# MotherBoard_PowerSupply.net
KiCad netlist of a schematic drawn in Altium Designer
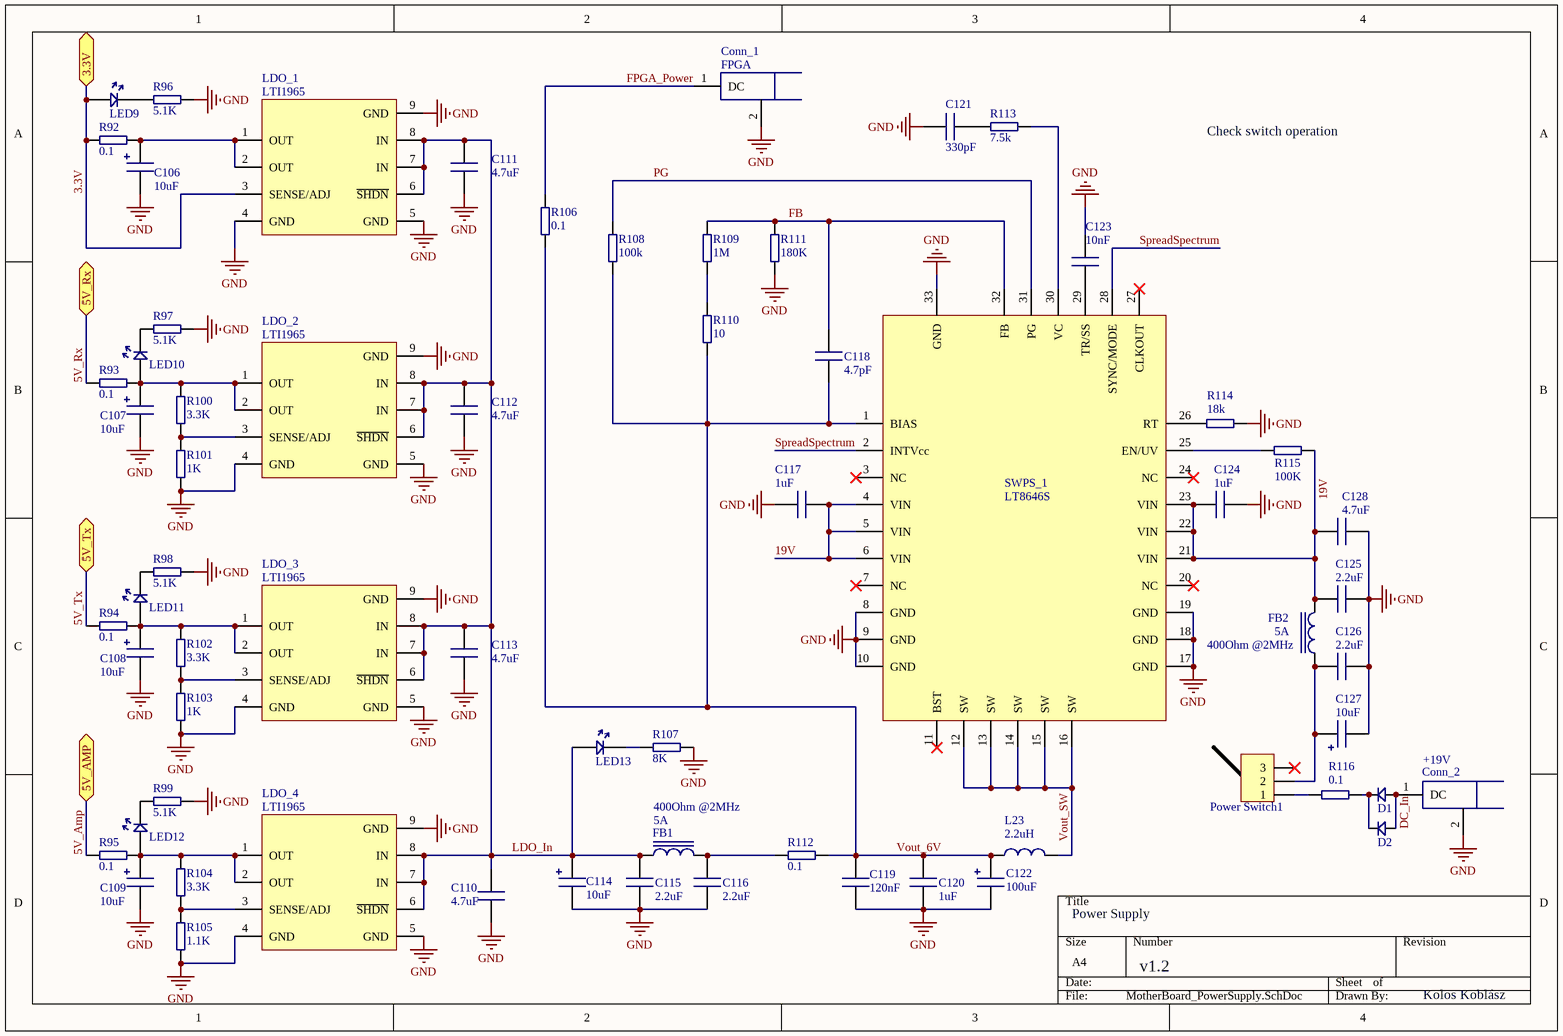
[diagram p0: MotherBoard_PowerSupply.SchDoc]

(export (version "E")
  (design (tool "Eeschema 10.0.6"))
  (components
    (comp (ref "C106")
      (value "10uF")
      (footprint "ELKO_CAP")
      (description "SMD Polarized Capacitor")
      (fields (field (name "Comment") "Cap2"))
      (libsource (lib "RadioProjectSchLib") (part "Cap2"))
    )
    (comp (ref "C107")
      (value "10uF")
      (footprint "ELKO_CAP")
      (description "SMD Polarized Capacitor")
      (fields (field (name "Comment") "Cap2"))
      (libsource (lib "RadioProjectSchLib") (part "Cap2"))
    )
    (comp (ref "C108")
      (value "10uF")
      (footprint "ELKO_CAP")
      (description "SMD Polarized Capacitor")
      (fields (field (name "Comment") "Cap2"))
      (libsource (lib "RadioProjectSchLib") (part "Cap2"))
    )
    (comp (ref "C109")
      (value "10uF")
      (footprint "ELKO_CAP")
      (description "SMD Polarized Capacitor")
      (fields (field (name "Comment") "Cap2"))
      (libsource (lib "RadioProjectSchLib") (part "Cap2"))
    )
    (comp (ref "C110")
      (value "4.7uF")
      (footprint "0805 SMD Passive")
      (description "SMD Capacitor")
      (fields (field (name "Comment") "Cap1"))
      (libsource (lib "RadioProjectSchLib") (part "Cap1"))
    )
    (comp (ref "C111")
      (value "4.7uF")
      (footprint "0805 SMD Passive")
      (description "SMD Capacitor")
      (fields (field (name "Comment") "Cap1"))
      (libsource (lib "RadioProjectSchLib") (part "Cap1"))
    )
    (comp (ref "C112")
      (value "4.7uF")
      (footprint "0805 SMD Passive")
      (description "SMD Capacitor")
      (fields (field (name "Comment") "Cap1"))
      (libsource (lib "RadioProjectSchLib") (part "Cap1"))
    )
    (comp (ref "C113")
      (value "4.7uF")
      (footprint "0805 SMD Passive")
      (description "SMD Capacitor")
      (fields (field (name "Comment") "Cap1"))
      (libsource (lib "RadioProjectSchLib") (part "Cap1"))
    )
    (comp (ref "C114")
      (value "10uF")
      (footprint "ELKO_CAP")
      (description "SMD Polarized Capacitor")
      (fields (field (name "Comment") "Cap2"))
      (libsource (lib "RadioProjectSchLib") (part "Cap2"))
    )
    (comp (ref "C115")
      (value "2.2uF")
      (footprint "0805 SMD Passive")
      (description "SMD Capacitor")
      (fields (field (name "Comment") "Cap1"))
      (libsource (lib "RadioProjectSchLib") (part "Cap1"))
    )
    (comp (ref "C116")
      (value "2.2uF")
      (footprint "0805 SMD Passive")
      (description "SMD Capacitor")
      (fields (field (name "Comment") "Cap1"))
      (libsource (lib "RadioProjectSchLib") (part "Cap1"))
    )
    (comp (ref "C117")
      (value "1uF")
      (footprint "0805 SMD Passive")
      (description "SMD Capacitor")
      (fields (field (name "Comment") "Cap1"))
      (libsource (lib "RadioProjectSchLib") (part "Cap1"))
    )
    (comp (ref "C118")
      (value "4.7pF")
      (footprint "0805 SMD Passive")
      (description "SMD Capacitor")
      (fields (field (name "Comment") "Cap1"))
      (libsource (lib "RadioProjectSchLib") (part "Cap1"))
    )
    (comp (ref "C119")
      (value "120nF")
      (footprint "0805 SMD Passive")
      (description "SMD Capacitor")
      (fields (field (name "Comment") "Cap1"))
      (libsource (lib "RadioProjectSchLib") (part "Cap1"))
    )
    (comp (ref "C120")
      (value "1uF")
      (footprint "0805 SMD Passive")
      (description "SMD Capacitor")
      (fields (field (name "Comment") "Cap1"))
      (libsource (lib "RadioProjectSchLib") (part "Cap1"))
    )
    (comp (ref "C121")
      (value "330pF")
      (footprint "0805 SMD Passive")
      (description "SMD Capacitor")
      (fields (field (name "Comment") "Cap1"))
      (libsource (lib "RadioProjectSchLib") (part "Cap1"))
    )
    (comp (ref "C122")
      (value "100uF")
      (footprint "ELKO_CAP")
      (description "SMD Polarized Capacitor")
      (fields (field (name "Comment") "Cap2"))
      (libsource (lib "RadioProjectSchLib") (part "Cap2"))
    )
    (comp (ref "C123")
      (value "10nF")
      (footprint "0805 SMD Passive")
      (description "SMD Capacitor")
      (fields (field (name "Comment") "Cap1"))
      (libsource (lib "RadioProjectSchLib") (part "Cap1"))
    )
    (comp (ref "C124")
      (value "1uF")
      (footprint "0805 SMD Passive")
      (description "SMD Capacitor")
      (fields (field (name "Comment") "Cap1"))
      (libsource (lib "RadioProjectSchLib") (part "Cap1"))
    )
    (comp (ref "C125")
      (value "2.2uF")
      (footprint "0805 SMD Passive")
      (description "SMD Capacitor")
      (fields (field (name "Comment") "Cap1"))
      (libsource (lib "RadioProjectSchLib") (part "Cap1"))
    )
    (comp (ref "C126")
      (value "2.2uF")
      (footprint "0805 SMD Passive")
      (description "SMD Capacitor")
      (fields (field (name "Comment") "Cap1"))
      (libsource (lib "RadioProjectSchLib") (part "Cap1"))
    )
    (comp (ref "C127")
      (value "10uF")
      (footprint "ELKO_CAP")
      (description "SMD Polarized Capacitor")
      (fields (field (name "Comment") "Cap2"))
      (libsource (lib "RadioProjectSchLib") (part "Cap2"))
    )
    (comp (ref "C128")
      (value "4.7uF")
      (footprint "0805 SMD Passive")
      (description "SMD Capacitor")
      (fields (field (name "Comment") "Cap1"))
      (libsource (lib "RadioProjectSchLib") (part "Cap1"))
    )
    (comp (ref "Conn_1")
      (value "FPGA")
      (footprint "DC_Connector")
      (description "Coaxial DC connector - female")
      (libsource (lib "RadioProjectSchLib") (part "DC_Connector"))
    )
    (comp (ref "Conn_2")
      (value "+19V")
      (footprint "DC_Connector")
      (description "Coaxial DC connector - female")
      (libsource (lib "RadioProjectSchLib") (part "DC_Connector"))
    )
    (comp (ref "D1")
      (value "Diode1")
      (footprint "SMB")
      (description "Diode")
      (fields (field (name "PARTNUMBER") "DO-2144AA"))
      (libsource (lib "RadioProjectSchLib") (part "Diode1"))
    )
    (comp (ref "D2")
      (value "Diode1")
      (footprint "SMB")
      (description "Diode")
      (fields (field (name "PARTNUMBER") "DO-214AA"))
      (libsource (lib "RadioProjectSchLib") (part "Diode1"))
    )
    (comp (ref "FB1")
      (value "400Ohm @2MHz")
      (footprint "FerritBead")
      (description "Ferrit Bead")
      (fields (field (name "MAXCURENT") "5A") (field (name "PARTNUMBER") "FB20022-4B-RC"))
      (libsource (lib "RadioProjectSchLib") (part "FerritBead"))
    )
    (comp (ref "FB2")
      (value "400Ohm @2MHz")
      (footprint "FerritBead")
      (description "Ferrit Bead")
      (fields (field (name "MAXCURENT") "5A") (field (name "PARTNUMBER") "FB20022-4B-RC"))
      (libsource (lib "") (part "FerritBead_1"))
    )
    (comp (ref "L23")
      (value "2.2uH")
      (footprint "SMD Inductor")
      (description "SMD Inductor")
      (fields (field (name "MANUFACTURER") "Coilcraft") (field (name "PARTNUMBER") "XEL-4030-222"))
      (libsource (lib "RadioProjectSchLib") (part "Ind1"))
    )
    (comp (ref "LDO_1")
      (value "LTI1965")
      (footprint "LT1965")
      (description "Low Dropout Linear Regulator")
      (fields (field (name "MANUFACTURER") "Analog Devices"))
      (libsource (lib "RadioProjectSchLib") (part "LTI1965"))
    )
    (comp (ref "LDO_2")
      (value "LTI1965")
      (footprint "LT1965")
      (description "Low Dropout Linear Regulator")
      (fields (field (name "MANUFACTURER") "Analog Devices"))
      (libsource (lib "RadioProjectSchLib") (part "LTI1965"))
    )
    (comp (ref "LDO_3")
      (value "LTI1965")
      (footprint "LT1965")
      (description "Low Dropout Linear Regulator")
      (fields (field (name "MANUFACTURER") "Analog Devices"))
      (libsource (lib "RadioProjectSchLib") (part "LTI1965"))
    )
    (comp (ref "LDO_4")
      (value "LTI1965")
      (footprint "LT1965")
      (description "Low Dropout Linear Regulator")
      (fields (field (name "MANUFACTURER") "Analog Devices"))
      (libsource (lib "RadioProjectSchLib") (part "LTI1965"))
    )
    (comp (ref "LED9")
      (value "+3.3V")
      (footprint "0805 SMD Passive")
      (description "Diode")
      (fields (field (name "MANUFACTURER") "LITEON") (field (name "PARTNUMBER") "LTST-C171KGKT"))
      (libsource (lib "RadioProjectSchLib") (part "LED_Green"))
    )
    (comp (ref "LED10")
      (value "+5V Rx")
      (footprint "0805 SMD Passive")
      (description "Diode")
      (fields (field (name "MANUFACTURER") "LITEON") (field (name "PARTNUMBER") "LTST-C171KGKT"))
      (libsource (lib "RadioProjectSchLib") (part "LED_Green"))
    )
    (comp (ref "LED11")
      (value "+5V Tx")
      (footprint "0805 SMD Passive")
      (description "Diode")
      (fields (field (name "MANUFACTURER") "LITEON") (field (name "PARTNUMBER") "LTST-C171KGKT"))
      (libsource (lib "RadioProjectSchLib") (part "LED_Green"))
    )
    (comp (ref "LED12")
      (value "+5V AMP")
      (footprint "0805 SMD Passive")
      (description "Diode")
      (fields (field (name "MANUFACTURER") "LITEON") (field (name "PARTNUMBER") "LTST-C171KGKT"))
      (libsource (lib "RadioProjectSchLib") (part "LED_Green"))
    )
    (comp (ref "LED13")
      (value "+6V")
      (footprint "0805 SMD Passive")
      (description "Diode")
      (fields (field (name "MANUFACTURER") "LITEON") (field (name "PARTNUMBER") "LTST-C171KGKT"))
      (libsource (lib "RadioProjectSchLib") (part "LED_Green"))
    )
    (comp (ref "Power Switch1")
      (value "Switch")
      (footprint "Switch")
      (description "3 state switch")
      (libsource (lib "RadioProjectSchLib") (part "Switch"))
    )
    (comp (ref "R92")
      (value "0.1")
      (footprint "0805 SMD Passive")
      (description "SMD Resistor")
      (fields (field (name "Comment") "Resistor"))
      (libsource (lib "RadioProjectSchLib") (part "Res1"))
    )
    (comp (ref "R93")
      (value "0.1")
      (footprint "0805 SMD Passive")
      (description "SMD Resistor")
      (fields (field (name "Comment") "Resistor"))
      (libsource (lib "RadioProjectSchLib") (part "Res1"))
    )
    (comp (ref "R94")
      (value "0.1")
      (footprint "0805 SMD Passive")
      (description "SMD Resistor")
      (fields (field (name "Comment") "Resistor"))
      (libsource (lib "RadioProjectSchLib") (part "Res1"))
    )
    (comp (ref "R95")
      (value "0.1")
      (footprint "0805 SMD Passive")
      (description "SMD Resistor")
      (fields (field (name "Comment") "Resistor"))
      (libsource (lib "RadioProjectSchLib") (part "Res1"))
    )
    (comp (ref "R96")
      (value "5.1K")
      (footprint "0805 SMD Passive")
      (description "SMD Resistor")
      (fields (field (name "Comment") "Resistor"))
      (libsource (lib "RadioProjectSchLib") (part "Res1"))
    )
    (comp (ref "R97")
      (value "5.1K")
      (footprint "0805 SMD Passive")
      (description "SMD Resistor")
      (fields (field (name "Comment") "Resistor"))
      (libsource (lib "RadioProjectSchLib") (part "Res1"))
    )
    (comp (ref "R98")
      (value "5.1K")
      (footprint "0805 SMD Passive")
      (description "SMD Resistor")
      (fields (field (name "Comment") "Resistor"))
      (libsource (lib "RadioProjectSchLib") (part "Res1"))
    )
    (comp (ref "R99")
      (value "5.1K")
      (footprint "0805 SMD Passive")
      (description "SMD Resistor")
      (fields (field (name "Comment") "Resistor"))
      (libsource (lib "RadioProjectSchLib") (part "Res1"))
    )
    (comp (ref "R100")
      (value "3.3K")
      (footprint "0805 SMD Passive")
      (description "SMD Resistor")
      (fields (field (name "Comment") "Resistor"))
      (libsource (lib "RadioProjectSchLib") (part "Res1"))
    )
    (comp (ref "R101")
      (value "1K")
      (footprint "0805 SMD Passive")
      (description "SMD Resistor")
      (fields (field (name "Comment") "Resistor"))
      (libsource (lib "RadioProjectSchLib") (part "Res1"))
    )
    (comp (ref "R102")
      (value "3.3K")
      (footprint "0805 SMD Passive")
      (description "SMD Resistor")
      (fields (field (name "Comment") "Resistor"))
      (libsource (lib "RadioProjectSchLib") (part "Res1"))
    )
    (comp (ref "R103")
      (value "1K")
      (footprint "0805 SMD Passive")
      (description "SMD Resistor")
      (fields (field (name "Comment") "Resistor"))
      (libsource (lib "RadioProjectSchLib") (part "Res1"))
    )
    (comp (ref "R104")
      (value "3.3K")
      (footprint "0805 SMD Passive")
      (description "SMD Resistor")
      (fields (field (name "Comment") "Resistor"))
      (libsource (lib "RadioProjectSchLib") (part "Res1"))
    )
    (comp (ref "R105")
      (value "1.1K")
      (footprint "0805 SMD Passive")
      (description "SMD Resistor")
      (fields (field (name "Comment") "Resistor"))
      (libsource (lib "RadioProjectSchLib") (part "Res1"))
    )
    (comp (ref "R106")
      (value "0.1")
      (footprint "0805 SMD Passive")
      (description "SMD Resistor")
      (fields (field (name "Comment") "Resistor"))
      (libsource (lib "RadioProjectSchLib") (part "Res1"))
    )
    (comp (ref "R107")
      (value "8K")
      (footprint "0805 SMD Passive")
      (description "SMD Resistor")
      (fields (field (name "Comment") "Resistor"))
      (libsource (lib "RadioProjectSchLib") (part "Res1"))
    )
    (comp (ref "R108")
      (value "100k")
      (footprint "0805 SMD Passive")
      (description "SMD Resistor")
      (fields (field (name "Comment") "Resistor"))
      (libsource (lib "RadioProjectSchLib") (part "Res1"))
    )
    (comp (ref "R109")
      (value "1M")
      (footprint "0805 SMD Passive")
      (description "SMD Resistor")
      (fields (field (name "Comment") "Resistor"))
      (libsource (lib "RadioProjectSchLib") (part "Res1"))
    )
    (comp (ref "R110")
      (value "10")
      (footprint "0805 SMD Passive")
      (description "SMD Resistor")
      (fields (field (name "Comment") "Resistor"))
      (libsource (lib "RadioProjectSchLib") (part "Res1"))
    )
    (comp (ref "R111")
      (value "180K")
      (footprint "0805 SMD Passive")
      (description "SMD Resistor")
      (fields (field (name "Comment") "Resistor"))
      (libsource (lib "RadioProjectSchLib") (part "Res1"))
    )
    (comp (ref "R112")
      (value "0.1")
      (footprint "0805 SMD Passive")
      (description "SMD Resistor")
      (fields (field (name "Comment") "Resistor"))
      (libsource (lib "RadioProjectSchLib") (part "Res1"))
    )
    (comp (ref "R113")
      (value "7.5k")
      (footprint "0805 SMD Passive")
      (description "SMD Resistor")
      (fields (field (name "Comment") "Resistor"))
      (libsource (lib "RadioProjectSchLib") (part "Res1"))
    )
    (comp (ref "R114")
      (value "18k")
      (footprint "0805 SMD Passive")
      (description "SMD Resistor")
      (fields (field (name "Comment") "Resistor"))
      (libsource (lib "RadioProjectSchLib") (part "Res1"))
    )
    (comp (ref "R115")
      (value "100K")
      (footprint "0805 SMD Passive")
      (description "SMD Resistor")
      (fields (field (name "Comment") "Resistor"))
      (libsource (lib "RadioProjectSchLib") (part "Res1"))
    )
    (comp (ref "R116")
      (value "0.1")
      (footprint "0805 SMD Passive")
      (description "SMD Resistor")
      (fields (field (name "Comment") "Resistor"))
      (libsource (lib "RadioProjectSchLib") (part "Res1"))
    )
    (comp (ref "SWPS_1")
      (value "LT8646S")
      (footprint "LT8646S")
      (description "Step-Down Silent Switcher Power Supply")
      (fields (field (name "MANUFACTURER") "Analog Devices"))
      (libsource (lib "RadioProjectSchLib") (part "LT8646S"))
    )
  )
  (nets
    (net (code "1") (name "/3.3V") (class "Default")
      (node (ref "LDO_1") (pin "3") (pinfunction "SENSE/ADJ_3") (pintype "passive"))
      (node (ref "LED9") (pin "2") (pinfunction "A_2") (pintype "passive"))
      (node (ref "R92") (pin "1") (pinfunction "*_1") (pintype "passive"))
    )
    (net (code "2") (name "/5V_Amp") (class "Default")
      (node (ref "R95") (pin "1") (pinfunction "*_1") (pintype "passive"))
    )
    (net (code "3") (name "/5V_Rx") (class "Default")
      (node (ref "R93") (pin "1") (pinfunction "*_1") (pintype "passive"))
    )
    (net (code "4") (name "/5V_Tx") (class "Default")
      (node (ref "R94") (pin "1") (pinfunction "*_1") (pintype "passive"))
    )
    (net (code "5") (name "/19V") (class "Default")
      (node (ref "C117") (pin "1") (pinfunction "*_1") (pintype "passive"))
      (node (ref "C124") (pin "1") (pinfunction "*_1") (pintype "passive"))
      (node (ref "C125") (pin "2") (pinfunction "*_2") (pintype "passive"))
      (node (ref "C128") (pin "2") (pinfunction "*_2") (pintype "passive"))
      (node (ref "FB2") (pin "1") (pinfunction "*_1") (pintype "passive"))
      (node (ref "R115") (pin "1") (pinfunction "*_1") (pintype "passive"))
      (node (ref "SWPS_1") (pin "21") (pinfunction "VIN_21") (pintype "passive"))
      (node (ref "SWPS_1") (pin "22") (pinfunction "VIN_22") (pintype "passive"))
      (node (ref "SWPS_1") (pin "23") (pinfunction "VIN_23") (pintype "passive"))
      (node (ref "SWPS_1") (pin "4") (pinfunction "VIN_4") (pintype "passive"))
      (node (ref "SWPS_1") (pin "5") (pinfunction "VIN_5") (pintype "passive"))
      (node (ref "SWPS_1") (pin "6") (pinfunction "VIN_6") (pintype "passive"))
    )
    (net (code "6") (name "/DC_In") (class "Default")
      (node (ref "Conn_2") (pin "1") (pinfunction "DC_1") (pintype "passive"))
      (node (ref "D1") (pin "2") (pinfunction "A_2") (pintype "passive"))
      (node (ref "D2") (pin "2") (pinfunction "A_2") (pintype "passive"))
    )
    (net (code "7") (name "/FB") (class "Default")
      (node (ref "C118") (pin "1") (pinfunction "*_1") (pintype "passive"))
      (node (ref "R109") (pin "1") (pinfunction "*_1") (pintype "passive"))
      (node (ref "R111") (pin "1") (pinfunction "*_1") (pintype "passive"))
      (node (ref "SWPS_1") (pin "32") (pinfunction "FB_32") (pintype "passive"))
    )
    (net (code "8") (name "/FPGA_Power") (class "Default")
      (node (ref "Conn_1") (pin "1") (pinfunction "DC_1") (pintype "passive"))
      (node (ref "R106") (pin "1") (pinfunction "*_1") (pintype "passive"))
    )
    (net (code "9") (name "/LDO_In") (class "Default")
      (node (ref "C110") (pin "2") (pinfunction "*_2") (pintype "passive"))
      (node (ref "C111") (pin "2") (pinfunction "*_2") (pintype "passive"))
      (node (ref "C112") (pin "2") (pinfunction "*_2") (pintype "passive"))
      (node (ref "C113") (pin "2") (pinfunction "*_2") (pintype "passive"))
      (node (ref "C114") (pin "1") (pinfunction "*_1") (pintype "passive"))
      (node (ref "C115") (pin "2") (pinfunction "*_2") (pintype "passive"))
      (node (ref "FB1") (pin "1") (pinfunction "*_1") (pintype "passive"))
      (node (ref "LDO_1") (pin "6") (pinfunction "~{SHDN}_6") (pintype "passive"))
      (node (ref "LDO_1") (pin "7") (pinfunction "IN_7") (pintype "passive"))
      (node (ref "LDO_1") (pin "8") (pinfunction "IN_8") (pintype "passive"))
      (node (ref "LDO_2") (pin "6") (pinfunction "~{SHDN}_6") (pintype "passive"))
      (node (ref "LDO_2") (pin "7") (pinfunction "IN_7") (pintype "passive"))
      (node (ref "LDO_2") (pin "8") (pinfunction "IN_8") (pintype "passive"))
      (node (ref "LDO_3") (pin "6") (pinfunction "~{SHDN}_6") (pintype "passive"))
      (node (ref "LDO_3") (pin "7") (pinfunction "IN_7") (pintype "passive"))
      (node (ref "LDO_3") (pin "8") (pinfunction "IN_8") (pintype "passive"))
      (node (ref "LDO_4") (pin "6") (pinfunction "~{SHDN}_6") (pintype "passive"))
      (node (ref "LDO_4") (pin "7") (pinfunction "IN_7") (pintype "passive"))
      (node (ref "LDO_4") (pin "8") (pinfunction "IN_8") (pintype "passive"))
      (node (ref "LED13") (pin "2") (pinfunction "A_2") (pintype "passive"))
    )
    (net (code "10") (name "/PG") (class "Default")
      (node (ref "R108") (pin "1") (pinfunction "*_1") (pintype "passive"))
      (node (ref "SWPS_1") (pin "31") (pinfunction "PG_31") (pintype "passive"))
    )
    (net (code "11") (name "/SpreadSpectrum") (class "Default")
      (node (ref "SWPS_1") (pin "2") (pinfunction "INTVcc_2") (pintype "passive"))
      (node (ref "SWPS_1") (pin "28") (pinfunction "SYNC/MODE_28") (pintype "passive"))
    )
    (net (code "12") (name "/Vout_6V") (class "Default")
      (node (ref "C118") (pin "2") (pinfunction "*_2") (pintype "passive"))
      (node (ref "C119") (pin "1") (pinfunction "*_1") (pintype "passive"))
      (node (ref "C120") (pin "1") (pinfunction "*_1") (pintype "passive"))
      (node (ref "C122") (pin "1") (pinfunction "*_1") (pintype "passive"))
      (node (ref "L23") (pin "1") (pinfunction "*_1") (pintype "passive"))
      (node (ref "R106") (pin "2") (pinfunction "*_2") (pintype "passive"))
      (node (ref "R108") (pin "2") (pinfunction "*_2") (pintype "passive"))
      (node (ref "R110") (pin "2") (pinfunction "*_2") (pintype "passive"))
      (node (ref "R112") (pin "2") (pinfunction "*_2") (pintype "passive"))
      (node (ref "SWPS_1") (pin "1") (pinfunction "BIAS_1") (pintype "passive"))
    )
    (net (code "13") (name "/Vout_SW") (class "Default")
      (node (ref "L23") (pin "2") (pinfunction "*_2") (pintype "passive"))
      (node (ref "SWPS_1") (pin "12") (pinfunction "SW_12") (pintype "passive"))
      (node (ref "SWPS_1") (pin "13") (pinfunction "SW_13") (pintype "passive"))
      (node (ref "SWPS_1") (pin "14") (pinfunction "SW_14") (pintype "passive"))
      (node (ref "SWPS_1") (pin "15") (pinfunction "SW_15") (pintype "passive"))
      (node (ref "SWPS_1") (pin "16") (pinfunction "SW_16") (pintype "passive"))
    )
    (net (code "14") (name "GND") (class "Default")
      (node (ref "C106") (pin "2") (pinfunction "*_2") (pintype "passive"))
      (node (ref "C107") (pin "2") (pinfunction "*_2") (pintype "passive"))
      (node (ref "C108") (pin "2") (pinfunction "*_2") (pintype "passive"))
      (node (ref "C109") (pin "2") (pinfunction "*_2") (pintype "passive"))
      (node (ref "C110") (pin "1") (pinfunction "*_1") (pintype "passive"))
      (node (ref "C111") (pin "1") (pinfunction "*_1") (pintype "passive"))
      (node (ref "C112") (pin "1") (pinfunction "*_1") (pintype "passive"))
      (node (ref "C113") (pin "1") (pinfunction "*_1") (pintype "passive"))
      (node (ref "C114") (pin "2") (pinfunction "*_2") (pintype "passive"))
      (node (ref "C115") (pin "1") (pinfunction "*_1") (pintype "passive"))
      (node (ref "C116") (pin "1") (pinfunction "*_1") (pintype "passive"))
      (node (ref "C117") (pin "2") (pinfunction "*_2") (pintype "passive"))
      (node (ref "C119") (pin "2") (pinfunction "*_2") (pintype "passive"))
      (node (ref "C120") (pin "2") (pinfunction "*_2") (pintype "passive"))
      (node (ref "C121") (pin "1") (pinfunction "*_1") (pintype "passive"))
      (node (ref "C122") (pin "2") (pinfunction "*_2") (pintype "passive"))
      (node (ref "C123") (pin "1") (pinfunction "*_1") (pintype "passive"))
      (node (ref "C124") (pin "2") (pinfunction "*_2") (pintype "passive"))
      (node (ref "C125") (pin "1") (pinfunction "*_1") (pintype "passive"))
      (node (ref "C126") (pin "1") (pinfunction "*_1") (pintype "passive"))
      (node (ref "C127") (pin "2") (pinfunction "*_2") (pintype "passive"))
      (node (ref "C128") (pin "1") (pinfunction "*_1") (pintype "passive"))
      (node (ref "Conn_1") (pin "2") (pinfunction "GND_2") (pintype "passive"))
      (node (ref "Conn_2") (pin "2") (pinfunction "GND_2") (pintype "passive"))
      (node (ref "LDO_1") (pin "4") (pinfunction "GND_4") (pintype "passive"))
      (node (ref "LDO_1") (pin "5") (pinfunction "GND_5") (pintype "passive"))
      (node (ref "LDO_1") (pin "9") (pinfunction "GND_9") (pintype "passive"))
      (node (ref "LDO_2") (pin "4") (pinfunction "GND_4") (pintype "passive"))
      (node (ref "LDO_2") (pin "5") (pinfunction "GND_5") (pintype "passive"))
      (node (ref "LDO_2") (pin "9") (pinfunction "GND_9") (pintype "passive"))
      (node (ref "LDO_3") (pin "4") (pinfunction "GND_4") (pintype "passive"))
      (node (ref "LDO_3") (pin "5") (pinfunction "GND_5") (pintype "passive"))
      (node (ref "LDO_3") (pin "9") (pinfunction "GND_9") (pintype "passive"))
      (node (ref "LDO_4") (pin "4") (pinfunction "GND_4") (pintype "passive"))
      (node (ref "LDO_4") (pin "5") (pinfunction "GND_5") (pintype "passive"))
      (node (ref "LDO_4") (pin "9") (pinfunction "GND_9") (pintype "passive"))
      (node (ref "R101") (pin "1") (pinfunction "*_1") (pintype "passive"))
      (node (ref "R103") (pin "1") (pinfunction "*_1") (pintype "passive"))
      (node (ref "R105") (pin "1") (pinfunction "*_1") (pintype "passive"))
      (node (ref "R107") (pin "2") (pinfunction "*_2") (pintype "passive"))
      (node (ref "R111") (pin "2") (pinfunction "*_2") (pintype "passive"))
      (node (ref "R114") (pin "2") (pinfunction "*_2") (pintype "passive"))
      (node (ref "R96") (pin "2") (pinfunction "*_2") (pintype "passive"))
      (node (ref "R97") (pin "2") (pinfunction "*_2") (pintype "passive"))
      (node (ref "R98") (pin "2") (pinfunction "*_2") (pintype "passive"))
      (node (ref "R99") (pin "2") (pinfunction "*_2") (pintype "passive"))
      (node (ref "SWPS_1") (pin "10") (pinfunction "GND_10") (pintype "passive"))
      (node (ref "SWPS_1") (pin "17") (pinfunction "GND_17") (pintype "passive"))
      (node (ref "SWPS_1") (pin "18") (pinfunction "GND_18") (pintype "passive"))
      (node (ref "SWPS_1") (pin "19") (pinfunction "GND_19") (pintype "passive"))
      (node (ref "SWPS_1") (pin "33") (pinfunction "GND_33") (pintype "passive"))
      (node (ref "SWPS_1") (pin "8") (pinfunction "GND_8") (pintype "passive"))
      (node (ref "SWPS_1") (pin "9") (pinfunction "GND_9") (pintype "passive"))
    )
    (net (code "15") (name "Net-(C106-*-Pad1)") (class "Default")
      (node (ref "C106") (pin "1") (pinfunction "*_1") (pintype "passive"))
      (node (ref "LDO_1") (pin "1") (pinfunction "OUT_1") (pintype "passive"))
      (node (ref "LDO_1") (pin "2") (pinfunction "OUT_2") (pintype "passive"))
      (node (ref "R92") (pin "2") (pinfunction "*_2") (pintype "passive"))
    )
    (net (code "16") (name "Net-(C116-*-Pad2)") (class "Default")
      (node (ref "C116") (pin "2") (pinfunction "*_2") (pintype "passive"))
      (node (ref "FB1") (pin "2") (pinfunction "*_2") (pintype "passive"))
      (node (ref "R112") (pin "1") (pinfunction "*_1") (pintype "passive"))
    )
    (net (code "17") (name "Net-(C121-*-Pad2)") (class "Default")
      (node (ref "C121") (pin "2") (pinfunction "*_2") (pintype "passive"))
      (node (ref "R113") (pin "1") (pinfunction "*_1") (pintype "passive"))
    )
    (net (code "18") (name "Net-(C126-*-Pad2)") (class "Default")
      (node (ref "C126") (pin "2") (pinfunction "*_2") (pintype "passive"))
      (node (ref "C127") (pin "1") (pinfunction "*_1") (pintype "passive"))
      (node (ref "FB2") (pin "2") (pinfunction "*_2") (pintype "passive"))
      (node (ref "Power Switch1") (pin "2") (pinfunction "2_2") (pintype "passive"))
    )
    (net (code "19") (name "Net-(D1-K)") (class "Default")
      (node (ref "D1") (pin "1") (pinfunction "K_1") (pintype "passive"))
      (node (ref "D2") (pin "1") (pinfunction "K_1") (pintype "passive"))
      (node (ref "R116") (pin "1") (pinfunction "*_1") (pintype "passive"))
    )
    (net (code "20") (name "Net-(LDO_2-SENSE{slash}ADJ)") (class "Default")
      (node (ref "LDO_2") (pin "3") (pinfunction "SENSE/ADJ_3") (pintype "passive"))
      (node (ref "R100") (pin "1") (pinfunction "*_1") (pintype "passive"))
      (node (ref "R101") (pin "2") (pinfunction "*_2") (pintype "passive"))
    )
    (net (code "21") (name "Net-(LDO_3-SENSE{slash}ADJ)") (class "Default")
      (node (ref "LDO_3") (pin "3") (pinfunction "SENSE/ADJ_3") (pintype "passive"))
      (node (ref "R102") (pin "1") (pinfunction "*_1") (pintype "passive"))
      (node (ref "R103") (pin "2") (pinfunction "*_2") (pintype "passive"))
    )
    (net (code "22") (name "Net-(LDO_4-SENSE{slash}ADJ)") (class "Default")
      (node (ref "LDO_4") (pin "3") (pinfunction "SENSE/ADJ_3") (pintype "passive"))
      (node (ref "R104") (pin "1") (pinfunction "*_1") (pintype "passive"))
      (node (ref "R105") (pin "2") (pinfunction "*_2") (pintype "passive"))
    )
    (net (code "23") (name "Net-(LED9-K)") (class "Default")
      (node (ref "LED9") (pin "1") (pinfunction "K_1") (pintype "passive"))
      (node (ref "R96") (pin "1") (pinfunction "*_1") (pintype "passive"))
    )
    (net (code "24") (name "Net-(LED10-A)") (class "Default")
      (node (ref "C107") (pin "1") (pinfunction "*_1") (pintype "passive"))
      (node (ref "LDO_2") (pin "1") (pinfunction "OUT_1") (pintype "passive"))
      (node (ref "LDO_2") (pin "2") (pinfunction "OUT_2") (pintype "passive"))
      (node (ref "LED10") (pin "2") (pinfunction "A_2") (pintype "passive"))
      (node (ref "R100") (pin "2") (pinfunction "*_2") (pintype "passive"))
      (node (ref "R93") (pin "2") (pinfunction "*_2") (pintype "passive"))
    )
    (net (code "25") (name "Net-(LED10-K)") (class "Default")
      (node (ref "LED10") (pin "1") (pinfunction "K_1") (pintype "passive"))
      (node (ref "R97") (pin "1") (pinfunction "*_1") (pintype "passive"))
    )
    (net (code "26") (name "Net-(LED11-A)") (class "Default")
      (node (ref "C108") (pin "1") (pinfunction "*_1") (pintype "passive"))
      (node (ref "LDO_3") (pin "1") (pinfunction "OUT_1") (pintype "passive"))
      (node (ref "LDO_3") (pin "2") (pinfunction "OUT_2") (pintype "passive"))
      (node (ref "LED11") (pin "2") (pinfunction "A_2") (pintype "passive"))
      (node (ref "R102") (pin "2") (pinfunction "*_2") (pintype "passive"))
      (node (ref "R94") (pin "2") (pinfunction "*_2") (pintype "passive"))
    )
    (net (code "27") (name "Net-(LED11-K)") (class "Default")
      (node (ref "LED11") (pin "1") (pinfunction "K_1") (pintype "passive"))
      (node (ref "R98") (pin "1") (pinfunction "*_1") (pintype "passive"))
    )
    (net (code "28") (name "Net-(LED12-A)") (class "Default")
      (node (ref "C109") (pin "1") (pinfunction "*_1") (pintype "passive"))
      (node (ref "LDO_4") (pin "1") (pinfunction "OUT_1") (pintype "passive"))
      (node (ref "LDO_4") (pin "2") (pinfunction "OUT_2") (pintype "passive"))
      (node (ref "LED12") (pin "2") (pinfunction "A_2") (pintype "passive"))
      (node (ref "R104") (pin "2") (pinfunction "*_2") (pintype "passive"))
      (node (ref "R95") (pin "2") (pinfunction "*_2") (pintype "passive"))
    )
    (net (code "29") (name "Net-(LED12-K)") (class "Default")
      (node (ref "LED12") (pin "1") (pinfunction "K_1") (pintype "passive"))
      (node (ref "R99") (pin "1") (pinfunction "*_1") (pintype "passive"))
    )
    (net (code "30") (name "Net-(LED13-K)") (class "Default")
      (node (ref "LED13") (pin "1") (pinfunction "K_1") (pintype "passive"))
      (node (ref "R107") (pin "1") (pinfunction "*_1") (pintype "passive"))
    )
    (net (code "31") (name "Net-(Power Switch1-Pad1)") (class "Default")
      (node (ref "Power Switch1") (pin "1") (pinfunction "1_1") (pintype "passive"))
      (node (ref "R116") (pin "2") (pinfunction "*_2") (pintype "passive"))
    )
    (net (code "32") (name "Net-(R109-*-Pad2)") (class "Default")
      (node (ref "R109") (pin "2") (pinfunction "*_2") (pintype "passive"))
      (node (ref "R110") (pin "1") (pinfunction "*_1") (pintype "passive"))
    )
    (net (code "33") (name "Net-(SWPS_1-EN{slash}UV)") (class "Default")
      (node (ref "R115") (pin "2") (pinfunction "*_2") (pintype "passive"))
      (node (ref "SWPS_1") (pin "25") (pinfunction "EN/UV_25") (pintype "passive"))
    )
    (net (code "34") (name "Net-(SWPS_1-RT)") (class "Default")
      (node (ref "R114") (pin "1") (pinfunction "*_1") (pintype "passive"))
      (node (ref "SWPS_1") (pin "26") (pinfunction "RT_26") (pintype "passive"))
    )
    (net (code "35") (name "Net-(SWPS_1-TR{slash}SS)") (class "Default")
      (node (ref "C123") (pin "2") (pinfunction "*_2") (pintype "passive"))
      (node (ref "SWPS_1") (pin "29") (pinfunction "TR/SS_29") (pintype "passive"))
    )
    (net (code "36") (name "Net-(SWPS_1-VC)") (class "Default")
      (node (ref "R113") (pin "2") (pinfunction "*_2") (pintype "passive"))
      (node (ref "SWPS_1") (pin "30") (pinfunction "VC_30") (pintype "passive"))
    )
    (net (code "37") (name "unconnected-(Power Switch1-Pad3)") (class "Default")
      (node (ref "Power Switch1") (pin "3") (pinfunction "3_3") (pintype "passive+no_connect"))
    )
    (net (code "38") (name "unconnected-(SWPS_1-BST-Pad11)") (class "Default")
      (node (ref "SWPS_1") (pin "11") (pinfunction "BST_11") (pintype "passive+no_connect"))
    )
    (net (code "39") (name "unconnected-(SWPS_1-CLKOUT-Pad27)") (class "Default")
      (node (ref "SWPS_1") (pin "27") (pinfunction "CLKOUT_27") (pintype "passive+no_connect"))
    )
    (net (code "40") (name "unconnected-(SWPS_1-NC-Pad3)") (class "Default")
      (node (ref "SWPS_1") (pin "3") (pinfunction "NC_3") (pintype "passive+no_connect"))
    )
    (net (code "41") (name "unconnected-(SWPS_1-NC-Pad7)") (class "Default")
      (node (ref "SWPS_1") (pin "7") (pinfunction "NC_7") (pintype "passive+no_connect"))
    )
    (net (code "42") (name "unconnected-(SWPS_1-NC-Pad20)") (class "Default")
      (node (ref "SWPS_1") (pin "20") (pinfunction "NC_20") (pintype "passive+no_connect"))
    )
    (net (code "43") (name "unconnected-(SWPS_1-NC-Pad24)") (class "Default")
      (node (ref "SWPS_1") (pin "24") (pinfunction "NC_24") (pintype "passive+no_connect"))
    )
  )
)
